# modbus_rtu_io.net
KiCad netlist of a schematic drawn in EAGLE
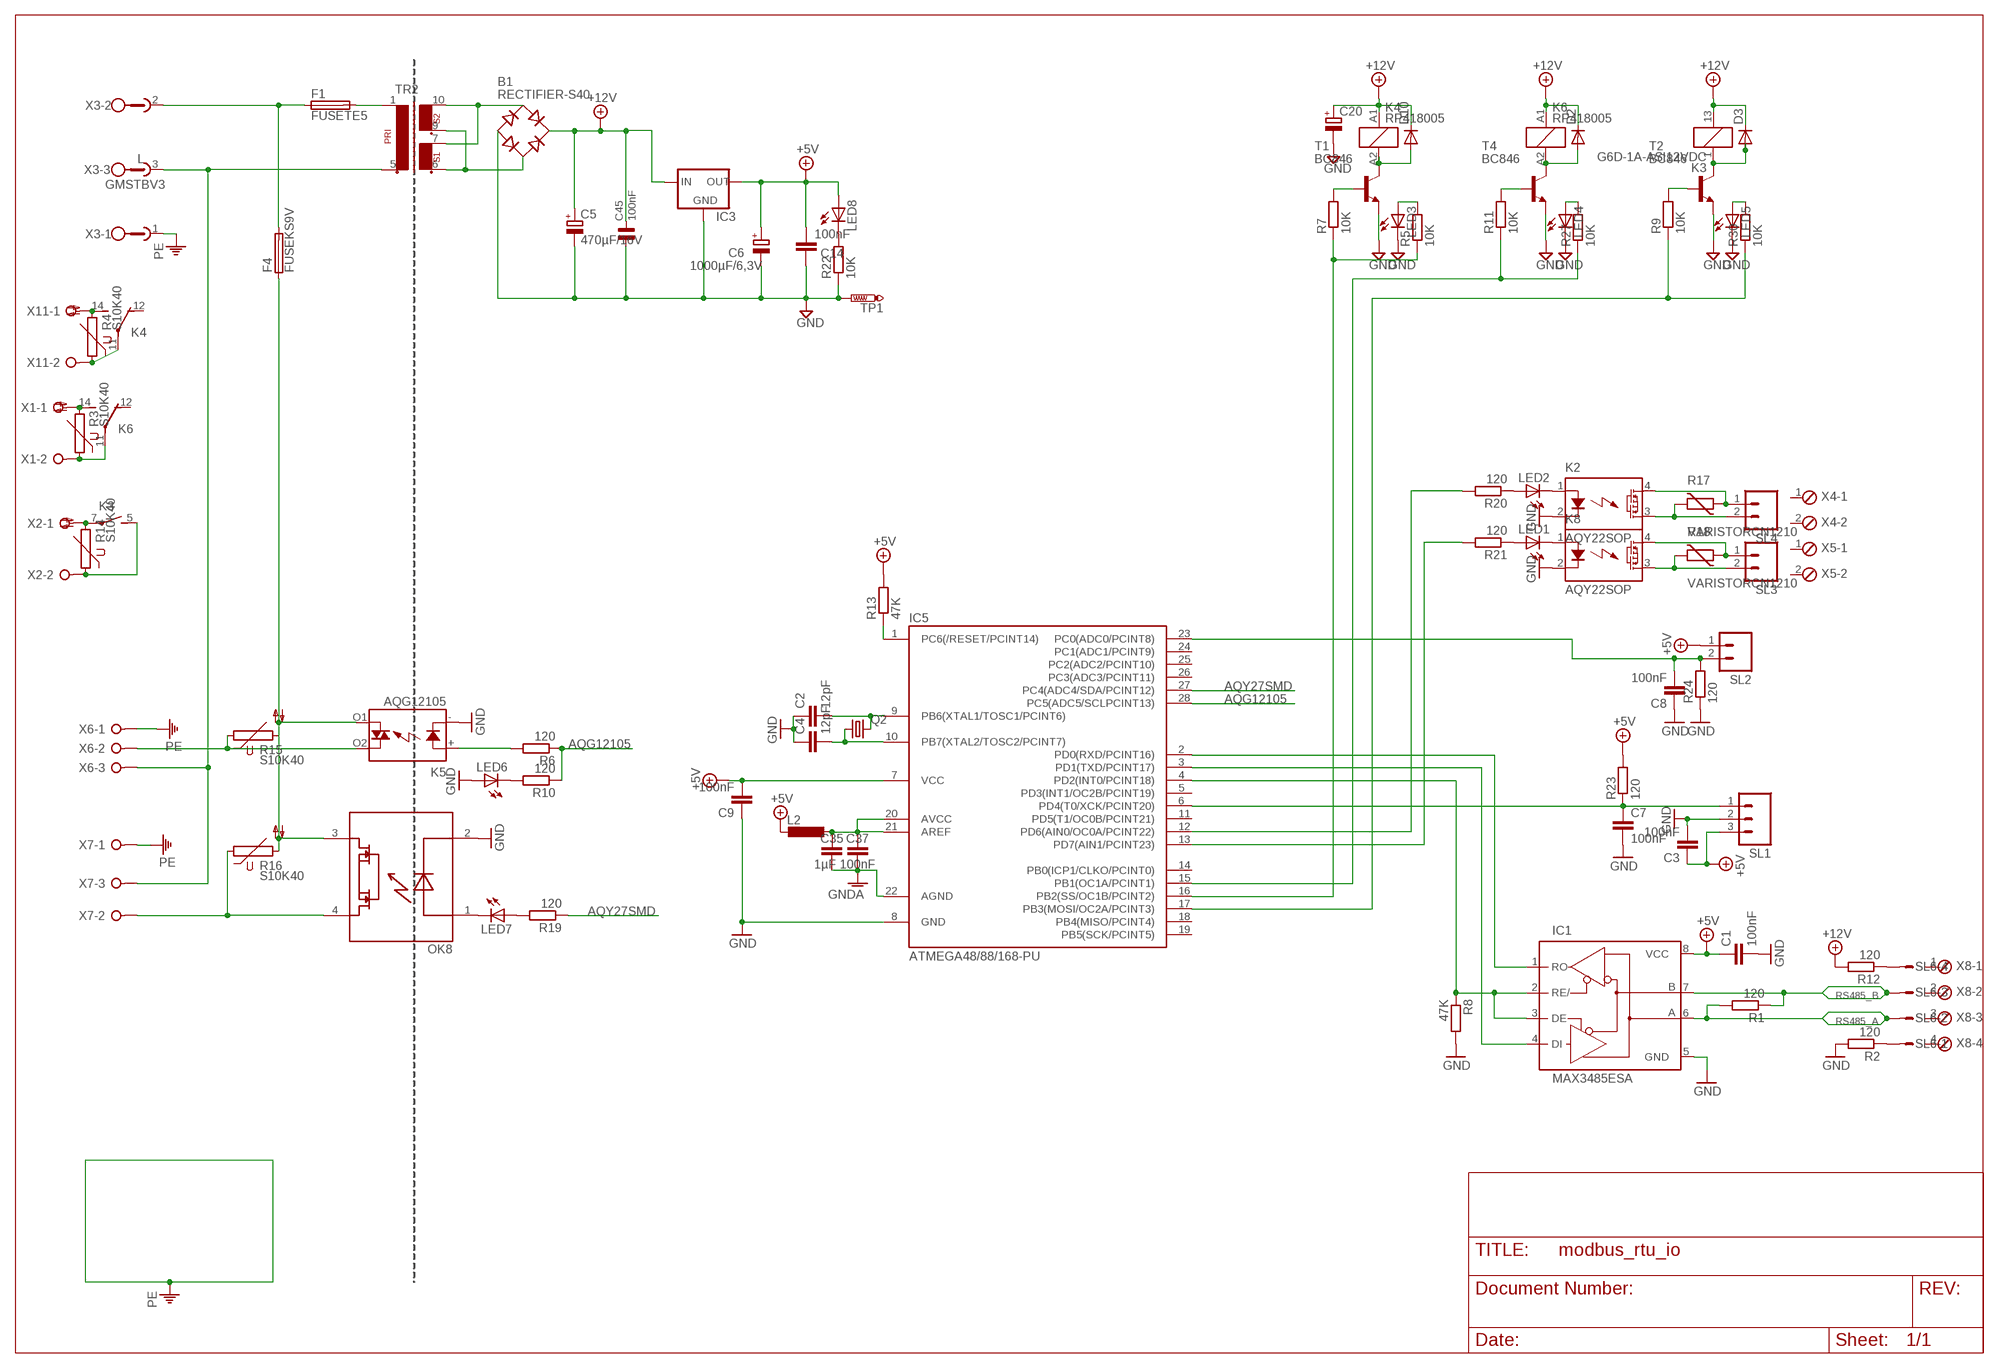
[diagram p0: schematic, sheet 1]

(export (version "E")
  (design (tool "Eeschema 10.0.6"))
  (components
    (comp (ref "B1")
      (value "RECTIFIER-S40")
      (footprint "eagle-import:TO-269AA")
      (libsource (lib "eagle-import") (part "RECTIFIER-S40"))
    )
    (comp (ref "C1")
      (value "100nF")
      (footprint "eagle-import:C0603")
      (libsource (lib "eagle-import") (part "C-EUC0603"))
    )
    (comp (ref "C2")
      (value "12pF")
      (footprint "eagle-import:C0805")
      (libsource (lib "eagle-import") (part "C-EUC0805"))
    )
    (comp (ref "C3")
      (value "100nF")
      (footprint "eagle-import:C0603")
      (libsource (lib "eagle-import") (part "C-EUC0603"))
    )
    (comp (ref "C4")
      (value "12pF")
      (footprint "eagle-import:C0805")
      (libsource (lib "eagle-import") (part "C-EUC0805"))
    )
    (comp (ref "C5")
      (value "470µF/16V")
      (footprint "eagle-import:E3,5-8")
      (libsource (lib "eagle-import") (part "CPOL-EUE3.5-8"))
    )
    (comp (ref "C6")
      (value "1000µF/6,3V")
      (footprint "eagle-import:E3,5-8")
      (libsource (lib "eagle-import") (part "CPOL-EUE3.5-8"))
    )
    (comp (ref "C7")
      (value "100nF")
      (footprint "eagle-import:C0603")
      (libsource (lib "eagle-import") (part "C-EUC0603"))
    )
    (comp (ref "C8")
      (value "100nF")
      (footprint "eagle-import:C0603")
      (libsource (lib "eagle-import") (part "C-EUC0603"))
    )
    (comp (ref "C9")
      (value "100nF")
      (footprint "eagle-import:C0603")
      (libsource (lib "eagle-import") (part "C-EUC0603"))
    )
    (comp (ref "C14")
      (value "100nF")
      (footprint "eagle-import:C1206")
      (libsource (lib "eagle-import") (part "C-EUC1206"))
    )
    (comp (ref "C20")
      (value "CPOL-EUE3.5-8")
      (footprint "eagle-import:E3,5-8")
      (libsource (lib "eagle-import") (part "CPOL-EUE3.5-8"))
    )
    (comp (ref "C35")
      (value "1µF")
      (footprint "eagle-import:C0603")
      (libsource (lib "eagle-import") (part "rcl-2_C-EUC0603"))
    )
    (comp (ref "C37")
      (value "100nF")
      (footprint "eagle-import:C0603")
      (libsource (lib "eagle-import") (part "rcl-2_C-EUC0603"))
    )
    (comp (ref "C45")
      (value "100nF")
      (footprint "eagle-import:C0805")
      (libsource (lib "eagle-import") (part "C0805"))
    )
    (comp (ref "D2")
      (value "DIODE-MINIMELF")
      (footprint "eagle-import:MINIMELF")
      (libsource (lib "eagle-import") (part "DIODE-MINIMELF"))
    )
    (comp (ref "D3")
      (value "DIODE-MINIMELF")
      (footprint "eagle-import:MINIMELF")
      (libsource (lib "eagle-import") (part "DIODE-MINIMELF"))
    )
    (comp (ref "D10")
      (value "DIODE-MINIMELF")
      (footprint "eagle-import:MINIMELF")
      (libsource (lib "eagle-import") (part "DIODE-MINIMELF"))
    )
    (comp (ref "F1")
      (value "FUSETE5")
      (footprint "eagle-import:TE5")
      (libsource (lib "eagle-import") (part "FUSETE5"))
    )
    (comp (ref "F4")
      (value "FUSEKS9V")
      (footprint "eagle-import:KS9V")
      (libsource (lib "eagle-import") (part "FUSEKS9V"))
    )
    (comp (ref "IC1")
      (value "MAX3485ESA")
      (footprint "eagle-import:SO08")
      (libsource (lib "eagle-import") (part "MAX34SA69E"))
    )
    (comp (ref "IC3")
      (value "78XXS")
      (footprint "eagle-import:78XXS")
      (libsource (lib "eagle-import") (part "78XXS"))
    )
    (comp (ref "IC5")
      (value "ATMEGA48/88/168-PU")
      (footprint "eagle-import:DIL28-3")
      (libsource (lib "eagle-import") (part "ATMEGA48/88/168-PU"))
    )
    (comp (ref "K2")
      (value "AQY22SOP")
      (footprint "eagle-import:SOP04")
      (libsource (lib "eagle-import") (part "AQYSOP22"))
    )
    (comp (ref "K3")
      (value "G6D-1A-ASI12VDC")
      (footprint "eagle-import:G6D")
      (libsource (lib "eagle-import") (part "G6D?-1A-ASI12VDC"))
    )
    (comp (ref "K4")
      (value "RP418005")
      (footprint "eagle-import:RT-C_O12A3.5")
      (libsource (lib "eagle-import") (part "RP?184005"))
    )
    (comp (ref "K5")
      (value "AQG12105")
      (footprint "eagle-import:AQG")
      (fields (field (name "MF") "AROMAT/ MATSUSHITA"))
      (libsource (lib "eagle-import") (part "AQG12105"))
    )
    (comp (ref "K6")
      (value "RP418005")
      (footprint "eagle-import:RT-C_O12A3.5")
      (libsource (lib "eagle-import") (part "RP?184005"))
    )
    (comp (ref "K8")
      (value "AQY22SOP")
      (footprint "eagle-import:SOP04")
      (libsource (lib "eagle-import") (part "AQYSOP22"))
    )
    (comp (ref "L2")
      (value "L-EUL0805")
      (footprint "eagle-import:L0805")
      (libsource (lib "eagle-import") (part "L-EUL0805"))
    )
    (comp (ref "LED1")
      (value "LED3MM")
      (footprint "eagle-import:LED3MM")
      (libsource (lib "eagle-import") (part "LED3MM"))
    )
    (comp (ref "LED2")
      (value "LED3MM")
      (footprint "eagle-import:LED3MM")
      (libsource (lib "eagle-import") (part "LED3MM"))
    )
    (comp (ref "LED3")
      (value "LED3MM")
      (footprint "eagle-import:LED3MM")
      (libsource (lib "eagle-import") (part "LED3MM"))
    )
    (comp (ref "LED4")
      (value "LED3MM")
      (footprint "eagle-import:LED3MM")
      (libsource (lib "eagle-import") (part "LED3MM"))
    )
    (comp (ref "LED5")
      (value "LED3MM")
      (footprint "eagle-import:LED3MM")
      (libsource (lib "eagle-import") (part "LED3MM"))
    )
    (comp (ref "LED6")
      (value "LED3MM")
      (footprint "eagle-import:LED3MM")
      (libsource (lib "eagle-import") (part "LED3MM"))
    )
    (comp (ref "LED7")
      (value "LED3MM")
      (footprint "eagle-import:LED3MM")
      (libsource (lib "eagle-import") (part "LED3MM"))
    )
    (comp (ref "LED8")
      (value "LED3MM")
      (footprint "eagle-import:LED3MM")
      (libsource (lib "eagle-import") (part "LED3MM"))
    )
    (comp (ref "OK8")
      (value "AQY280")
      (footprint "eagle-import:DIL4-SMD")
      (libsource (lib "eagle-import") (part "AQY280"))
    )
    (comp (ref "Q2")
      (value "CRYTALHC49S")
      (footprint "eagle-import:HC49_S")
      (libsource (lib "eagle-import") (part "CRYTALHC49S"))
    )
    (comp (ref "R1")
      (value "120")
      (footprint "eagle-import:R0603")
      (libsource (lib "eagle-import") (part "R-EU_R0603"))
    )
    (comp (ref "R2")
      (value "120")
      (footprint "eagle-import:R0603")
      (libsource (lib "eagle-import") (part "R-EU_R0603"))
    )
    (comp (ref "R3")
      (value "S10K40")
      (footprint "eagle-import:S10K40")
      (libsource (lib "eagle-import") (part "S10K40"))
    )
    (comp (ref "R4")
      (value "S10K40")
      (footprint "eagle-import:S10K40")
      (libsource (lib "eagle-import") (part "S10K40"))
    )
    (comp (ref "R5")
      (value "10K")
      (footprint "eagle-import:R0603")
      (libsource (lib "eagle-import") (part "R-EU_R0603"))
    )
    (comp (ref "R6")
      (value "120")
      (footprint "eagle-import:R0603")
      (libsource (lib "eagle-import") (part "R-EU_R0603"))
    )
    (comp (ref "R7")
      (value "10K")
      (footprint "eagle-import:R0603")
      (libsource (lib "eagle-import") (part "R-EU_R0603"))
    )
    (comp (ref "R8")
      (value "47K")
      (footprint "eagle-import:R0603")
      (libsource (lib "eagle-import") (part "R-EU_R0603"))
    )
    (comp (ref "R9")
      (value "10K")
      (footprint "eagle-import:R0603")
      (libsource (lib "eagle-import") (part "R-EU_R0603"))
    )
    (comp (ref "R10")
      (value "120")
      (footprint "eagle-import:R0603")
      (libsource (lib "eagle-import") (part "R-EU_R0603"))
    )
    (comp (ref "R11")
      (value "10K")
      (footprint "eagle-import:R0603")
      (libsource (lib "eagle-import") (part "R-EU_R0603"))
    )
    (comp (ref "R12")
      (value "120")
      (footprint "eagle-import:R0603")
      (libsource (lib "eagle-import") (part "R-EU_R0603"))
    )
    (comp (ref "R13")
      (value "47K")
      (footprint "eagle-import:R0603")
      (libsource (lib "eagle-import") (part "R-EU_R0603"))
    )
    (comp (ref "R14")
      (value "S10K40")
      (footprint "eagle-import:S10K40")
      (libsource (lib "eagle-import") (part "S10K40"))
    )
    (comp (ref "R15")
      (value "S10K40")
      (footprint "eagle-import:S10K40")
      (libsource (lib "eagle-import") (part "S10K40"))
    )
    (comp (ref "R16")
      (value "S10K40")
      (footprint "eagle-import:S10K40")
      (libsource (lib "eagle-import") (part "S10K40"))
    )
    (comp (ref "R17")
      (value "VARISTORCN1210")
      (footprint "eagle-import:CT_CN1210")
      (libsource (lib "eagle-import") (part "VARISTORCN1210"))
    )
    (comp (ref "R18")
      (value "VARISTORCN1210")
      (footprint "eagle-import:CT_CN1210")
      (libsource (lib "eagle-import") (part "VARISTORCN1210"))
    )
    (comp (ref "R19")
      (value "120")
      (footprint "eagle-import:R0603")
      (libsource (lib "eagle-import") (part "R-EU_R0603"))
    )
    (comp (ref "R20")
      (value "120")
      (footprint "eagle-import:R0603")
      (libsource (lib "eagle-import") (part "R-EU_R0603"))
    )
    (comp (ref "R21")
      (value "120")
      (footprint "eagle-import:R0603")
      (libsource (lib "eagle-import") (part "R-EU_R0603"))
    )
    (comp (ref "R22")
      (value "10K")
      (footprint "eagle-import:R0603")
      (libsource (lib "eagle-import") (part "R-EU_R0603"))
    )
    (comp (ref "R23")
      (value "120")
      (footprint "eagle-import:R0603")
      (libsource (lib "eagle-import") (part "R-EU_R0603"))
    )
    (comp (ref "R24")
      (value "120")
      (footprint "eagle-import:R0603")
      (libsource (lib "eagle-import") (part "R-EU_R0603"))
    )
    (comp (ref "R27")
      (value "10K")
      (footprint "eagle-import:R0603")
      (libsource (lib "eagle-import") (part "R-EU_R0603"))
    )
    (comp (ref "R30")
      (value "10K")
      (footprint "eagle-import:R0603")
      (libsource (lib "eagle-import") (part "R-EU_R0603"))
    )
    (comp (ref "SL1")
      (value "M03")
      (footprint "eagle-import:03P")
      (libsource (lib "eagle-import") (part "M03"))
    )
    (comp (ref "SL2")
      (value "M02")
      (footprint "eagle-import:02P")
      (libsource (lib "eagle-import") (part "M02"))
    )
    (comp (ref "SL3")
      (value "M02")
      (footprint "eagle-import:02P")
      (libsource (lib "eagle-import") (part "M02"))
    )
    (comp (ref "SL4")
      (value "M02")
      (footprint "eagle-import:02P")
      (libsource (lib "eagle-import") (part "M02"))
    )
    (comp (ref "SL6")
      (value "M04S")
      (footprint "eagle-import:04P")
      (libsource (lib "eagle-import") (part "M04S"))
    )
    (comp (ref "T1")
      (value "BC846")
      (footprint "eagle-import:SOT23")
      (libsource (lib "eagle-import") (part "BC846"))
    )
    (comp (ref "T2")
      (value "BC846")
      (footprint "eagle-import:SOT23")
      (libsource (lib "eagle-import") (part "BC846"))
    )
    (comp (ref "T4")
      (value "BC846")
      (footprint "eagle-import:SOT23")
      (libsource (lib "eagle-import") (part "BC846"))
    )
    (comp (ref "TP1")
      (value "PTR1PAD1-13")
      (footprint "eagle-import:P1-13")
      (libsource (lib "eagle-import") (part "PTR1PAD1-13"))
    )
    (comp (ref "TR2")
      (value "EI30-2")
      (footprint "eagle-import:EI30-2")
      (libsource (lib "eagle-import") (part "EI30-2"))
    )
    (comp (ref "X1")
      (value "W237-02P")
      (footprint "eagle-import:W237-132")
      (libsource (lib "eagle-import") (part "W237-02P"))
    )
    (comp (ref "X2")
      (value "W237-02P")
      (footprint "eagle-import:W237-132")
      (libsource (lib "eagle-import") (part "W237-02P"))
    )
    (comp (ref "X3")
      (value "GMSTBV3")
      (footprint "eagle-import:GMSTBV3")
      (fields (field (name "MPN") "GMSTBVA2,5/3-G-7,62"))
      (libsource (lib "eagle-import") (part "GMSTBV3"))
    )
    (comp (ref "X4")
      (value "MPT2")
      (footprint "eagle-import:2POL254")
      (libsource (lib "eagle-import") (part "MPT2"))
    )
    (comp (ref "X5")
      (value "MPT2")
      (footprint "eagle-import:2POL254")
      (libsource (lib "eagle-import") (part "MPT2"))
    )
    (comp (ref "X6")
      (value "W237-03P")
      (footprint "eagle-import:W237-133")
      (libsource (lib "eagle-import") (part "W237-03P"))
    )
    (comp (ref "X7")
      (value "W237-03P")
      (footprint "eagle-import:W237-133")
      (libsource (lib "eagle-import") (part "W237-03P"))
    )
    (comp (ref "X8")
      (value "MPT4")
      (footprint "eagle-import:4POL254")
      (libsource (lib "eagle-import") (part "MPT4"))
    )
    (comp (ref "X11")
      (value "W237-02P")
      (footprint "eagle-import:W237-132")
      (libsource (lib "eagle-import") (part "W237-02P"))
    )
  )
  (nets
    (net (code "1") (name "+5V") (class "Default")
      (node (ref "C1") (pin "1") (pinfunction "1_1") (pintype "passive"))
      (node (ref "C14") (pin "2") (pinfunction "2_2") (pintype "passive"))
      (node (ref "C3") (pin "1") (pinfunction "1_1") (pintype "passive"))
      (node (ref "C6") (pin "+") (pinfunction "+_+") (pintype "passive"))
      (node (ref "C9") (pin "2") (pinfunction "2_2") (pintype "passive"))
      (node (ref "IC1") (pin "8") (pinfunction "VCC_8") (pintype "power_in"))
      (node (ref "IC3") (pin "OUT") (pinfunction "OUT_OUT") (pintype "passive"))
      (node (ref "IC5") (pin "7") (pinfunction "VCC_7") (pintype "power_in"))
      (node (ref "L2") (pin "2") (pinfunction "2_2") (pintype "passive"))
      (node (ref "LED8") (pin "A") (pinfunction "A_A") (pintype "passive"))
      (node (ref "R13") (pin "2") (pinfunction "2_2") (pintype "passive"))
      (node (ref "R23") (pin "2") (pinfunction "2_2") (pintype "passive"))
      (node (ref "SL1") (pin "3") (pinfunction "3_3") (pintype "passive"))
      (node (ref "SL2") (pin "1") (pinfunction "1_1") (pintype "passive"))
    )
    (net (code "2") (name "+12V") (class "Default")
      (node (ref "B1") (pin "+") (pinfunction "+_+") (pintype "passive"))
      (node (ref "C20") (pin "+") (pinfunction "+_+") (pintype "passive"))
      (node (ref "C45") (pin "2") (pinfunction "2_2") (pintype "passive"))
      (node (ref "C5") (pin "+") (pinfunction "+_+") (pintype "passive"))
      (node (ref "D10") (pin "C") (pinfunction "C_C") (pintype "passive"))
      (node (ref "D2") (pin "C") (pinfunction "C_C") (pintype "passive"))
      (node (ref "D3") (pin "C") (pinfunction "C_C") (pintype "passive"))
      (node (ref "IC3") (pin "IN") (pinfunction "IN_IN") (pintype "input"))
      (node (ref "K3") (pin "13") (pinfunction "2_13") (pintype "passive"))
      (node (ref "K4") (pin "A1") (pinfunction "1_A1") (pintype "passive"))
      (node (ref "K6") (pin "A1") (pinfunction "1_A1") (pintype "passive"))
      (node (ref "R12") (pin "2") (pinfunction "2_2") (pintype "passive"))
    )
    (net (code "3") (name "/AQG12105") (class "Default")
      (node (ref "IC5") (pin "28") (pinfunction "PC5(ADC5/SCLPCINT13)_28") (pintype "bidirectional"))
      (node (ref "R10") (pin "1") (pinfunction "1_1") (pintype "passive"))
      (node (ref "R6") (pin "1") (pinfunction "1_1") (pintype "passive"))
    )
    (net (code "4") (name "/AQY27SMD") (class "Default")
      (node (ref "IC5") (pin "27") (pinfunction "PC4(ADC4/SDA/PCINT12)_27") (pintype "bidirectional"))
      (node (ref "R19") (pin "1") (pinfunction "1_1") (pintype "passive"))
    )
    (net (code "5") (name "/L") (class "Default")
      (node (ref "F1") (pin "1") (pinfunction "1_1") (pintype "passive"))
      (node (ref "F4") (pin "2") (pinfunction "2_2") (pintype "passive"))
      (node (ref "X3") (pin "2") (pinfunction "1_2") (pintype "passive"))
    )
    (net (code "6") (name "/RS485_A") (class "Default")
      (node (ref "IC1") (pin "6") (pinfunction "A_6") (pintype "passive"))
      (node (ref "R1") (pin "2") (pinfunction "2_2") (pintype "passive"))
      (node (ref "SL6") (pin "2") (pinfunction "S_2") (pintype "passive"))
    )
    (net (code "7") (name "/RS485_B") (class "Default")
      (node (ref "IC1") (pin "7") (pinfunction "B_7") (pintype "passive"))
      (node (ref "R1") (pin "1") (pinfunction "1_1") (pintype "passive"))
      (node (ref "SL6") (pin "3") (pinfunction "S_3") (pintype "passive"))
    )
    (net (code "8") (name "GND") (class "Default")
      (node (ref "B1") (pin "-") (pinfunction "-_-") (pintype "passive"))
      (node (ref "C1") (pin "2") (pinfunction "2_2") (pintype "passive"))
      (node (ref "C14") (pin "1") (pinfunction "1_1") (pintype "passive"))
      (node (ref "C2") (pin "1") (pinfunction "1_1") (pintype "passive"))
      (node (ref "C20") (pin "-") (pinfunction "-_-") (pintype "passive"))
      (node (ref "C3") (pin "2") (pinfunction "2_2") (pintype "passive"))
      (node (ref "C4") (pin "1") (pinfunction "1_1") (pintype "passive"))
      (node (ref "C45") (pin "1") (pinfunction "1_1") (pintype "passive"))
      (node (ref "C5") (pin "-") (pinfunction "-_-") (pintype "passive"))
      (node (ref "C6") (pin "-") (pinfunction "-_-") (pintype "passive"))
      (node (ref "C7") (pin "2") (pinfunction "2_2") (pintype "passive"))
      (node (ref "C8") (pin "1") (pinfunction "1_1") (pintype "passive"))
      (node (ref "C9") (pin "1") (pinfunction "1_1") (pintype "passive"))
      (node (ref "IC1") (pin "5") (pinfunction "GND_5") (pintype "power_in"))
      (node (ref "IC3") (pin "GND") (pinfunction "GND_GND") (pintype "input"))
      (node (ref "IC5") (pin "8") (pinfunction "GND_8") (pintype "power_in"))
      (node (ref "K2") (pin "2") (pinfunction "K_2") (pintype "passive"))
      (node (ref "K5") (pin "-") (pinfunction "K_-") (pintype "passive"))
      (node (ref "K8") (pin "2") (pinfunction "K_2") (pintype "passive"))
      (node (ref "LED3") (pin "K") (pinfunction "C_K") (pintype "passive"))
      (node (ref "LED4") (pin "K") (pinfunction "C_K") (pintype "passive"))
      (node (ref "LED5") (pin "K") (pinfunction "C_K") (pintype "passive"))
      (node (ref "LED6") (pin "A") (pinfunction "A_A") (pintype "passive"))
      (node (ref "OK8") (pin "2") (pinfunction "2_2") (pintype "passive"))
      (node (ref "R2") (pin "2") (pinfunction "2_2") (pintype "passive"))
      (node (ref "R22") (pin "1") (pinfunction "1_1") (pintype "passive"))
      (node (ref "R24") (pin "1") (pinfunction "1_1") (pintype "passive"))
      (node (ref "R8") (pin "2") (pinfunction "2_2") (pintype "passive"))
      (node (ref "SL1") (pin "2") (pinfunction "2_2") (pintype "passive"))
      (node (ref "T1") (pin "2") (pinfunction "E_2") (pintype "passive"))
      (node (ref "T2") (pin "2") (pinfunction "E_2") (pintype "passive"))
      (node (ref "T4") (pin "2") (pinfunction "E_2") (pintype "passive"))
      (node (ref "TP1") (pin "TP") (pinfunction "TP_TP") (pintype "input"))
    )
    (net (code "9") (name "GNDA") (class "Default")
      (node (ref "C35") (pin "2") (pinfunction "2_2") (pintype "passive"))
      (node (ref "C37") (pin "2") (pinfunction "2_2") (pintype "passive"))
      (node (ref "IC5") (pin "22") (pinfunction "AGND_22") (pintype "power_in"))
    )
    (net (code "10") (name "Net-(F1-Pad2)") (class "Default")
      (node (ref "F1") (pin "2") (pinfunction "2_2") (pintype "passive"))
      (node (ref "TR2") (pin "1") (pinfunction "1_1") (pintype "passive"))
    )
    (net (code "11") (name "Net-(IC1-DE)") (class "Default")
      (node (ref "IC1") (pin "2") (pinfunction "RE/_2") (pintype "input"))
      (node (ref "IC1") (pin "3") (pinfunction "DE_3") (pintype "input"))
      (node (ref "IC5") (pin "4") (pinfunction "PD2(INT0/PCINT18)_4") (pintype "bidirectional"))
      (node (ref "R8") (pin "1") (pinfunction "1_1") (pintype "passive"))
    )
    (net (code "12") (name "Net-(IC1-DI)") (class "Default")
      (node (ref "IC1") (pin "4") (pinfunction "DI_4") (pintype "input"))
      (node (ref "IC5") (pin "3") (pinfunction "PD1(TXD/PCINT17)_3") (pintype "bidirectional"))
    )
    (net (code "13") (name "Net-(IC1-RO)") (class "Default")
      (node (ref "IC1") (pin "1") (pinfunction "RO_1") (pintype "output"))
      (node (ref "IC5") (pin "2") (pinfunction "PD0(RXD/PCINT16)_2") (pintype "bidirectional"))
    )
    (net (code "14") (name "Net-(IC5-AREF)") (class "Default")
      (node (ref "C35") (pin "1") (pinfunction "1_1") (pintype "passive"))
      (node (ref "C37") (pin "1") (pinfunction "1_1") (pintype "passive"))
      (node (ref "IC5") (pin "20") (pinfunction "AVCC_20") (pintype "passive"))
      (node (ref "IC5") (pin "21") (pinfunction "AREF_21") (pintype "passive"))
      (node (ref "L2") (pin "1") (pinfunction "1_1") (pintype "passive"))
    )
    (net (code "15") (name "Net-(IC5-PB1(OC1A{slash}PCINT1))") (class "Default")
      (node (ref "IC5") (pin "15") (pinfunction "PB1(OC1A/PCINT1)_15") (pintype "bidirectional"))
      (node (ref "R11") (pin "1") (pinfunction "1_1") (pintype "passive"))
      (node (ref "R27") (pin "1") (pinfunction "1_1") (pintype "passive"))
    )
    (net (code "16") (name "Net-(IC5-PB2(SS{slash}OC1B{slash}PCINT2))") (class "Default")
      (node (ref "IC5") (pin "16") (pinfunction "PB2(SS/OC1B/PCINT2)_16") (pintype "bidirectional"))
      (node (ref "R5") (pin "1") (pinfunction "1_1") (pintype "passive"))
      (node (ref "R7") (pin "1") (pinfunction "1_1") (pintype "passive"))
    )
    (net (code "17") (name "Net-(IC5-PB3(MOSI{slash}OC2A{slash}PCINT3))") (class "Default")
      (node (ref "IC5") (pin "17") (pinfunction "PB3(MOSI/OC2A/PCINT3)_17") (pintype "bidirectional"))
      (node (ref "R30") (pin "1") (pinfunction "1_1") (pintype "passive"))
      (node (ref "R9") (pin "1") (pinfunction "1_1") (pintype "passive"))
    )
    (net (code "18") (name "Net-(IC5-PB6(XTAL1{slash}TOSC1{slash}PCINT6))") (class "Default")
      (node (ref "C2") (pin "2") (pinfunction "2_2") (pintype "passive"))
      (node (ref "IC5") (pin "9") (pinfunction "PB6(XTAL1/TOSC1/PCINT6)_9") (pintype "bidirectional"))
      (node (ref "Q2") (pin "2") (pinfunction "2_2") (pintype "passive"))
    )
    (net (code "19") (name "Net-(IC5-PB7(XTAL2{slash}TOSC2{slash}PCINT7))") (class "Default")
      (node (ref "C4") (pin "2") (pinfunction "2_2") (pintype "passive"))
      (node (ref "IC5") (pin "10") (pinfunction "PB7(XTAL2/TOSC2/PCINT7)_10") (pintype "bidirectional"))
      (node (ref "Q2") (pin "1") (pinfunction "1_1") (pintype "passive"))
    )
    (net (code "20") (name "Net-(IC5-PC0(ADC0{slash}PCINT8))") (class "Default")
      (node (ref "C8") (pin "2") (pinfunction "2_2") (pintype "passive"))
      (node (ref "IC5") (pin "23") (pinfunction "PC0(ADC0/PCINT8)_23") (pintype "bidirectional"))
      (node (ref "R24") (pin "2") (pinfunction "2_2") (pintype "passive"))
      (node (ref "SL2") (pin "2") (pinfunction "2_2") (pintype "passive"))
    )
    (net (code "21") (name "Net-(IC5-PC6({slash}RESET{slash}PCINT14))") (class "Default")
      (node (ref "IC5") (pin "1") (pinfunction "PC6(/RESET/PCINT14)_1") (pintype "bidirectional"))
      (node (ref "R13") (pin "1") (pinfunction "1_1") (pintype "passive"))
    )
    (net (code "22") (name "Net-(IC5-PD4(T0{slash}XCK{slash}PCINT20))") (class "Default")
      (node (ref "C7") (pin "1") (pinfunction "1_1") (pintype "passive"))
      (node (ref "IC5") (pin "6") (pinfunction "PD4(T0/XCK/PCINT20)_6") (pintype "bidirectional"))
      (node (ref "R23") (pin "1") (pinfunction "1_1") (pintype "passive"))
      (node (ref "SL1") (pin "1") (pinfunction "1_1") (pintype "passive"))
    )
    (net (code "23") (name "Net-(IC5-PD6(AIN0{slash}OC0A{slash}PCINT22))") (class "Default")
      (node (ref "IC5") (pin "12") (pinfunction "PD6(AIN0/OC0A/PCINT22)_12") (pintype "bidirectional"))
      (node (ref "R20") (pin "2") (pinfunction "2_2") (pintype "passive"))
    )
    (net (code "24") (name "Net-(IC5-PD7(AIN1{slash}PCINT23))") (class "Default")
      (node (ref "IC5") (pin "13") (pinfunction "PD7(AIN1/PCINT23)_13") (pintype "bidirectional"))
      (node (ref "R21") (pin "2") (pinfunction "2_2") (pintype "passive"))
    )
    (net (code "25") (name "Net-(K2-A)") (class "Default")
      (node (ref "K2") (pin "1") (pinfunction "A_1") (pintype "passive"))
      (node (ref "LED2") (pin "K") (pinfunction "C_K") (pintype "passive"))
    )
    (net (code "26") (name "Net-(K2-DS1)") (class "Default")
      (node (ref "K2") (pin "4") (pinfunction "DS1_4") (pintype "passive"))
      (node (ref "R17") (pin "1") (pinfunction "1_1") (pintype "passive"))
      (node (ref "SL4") (pin "1") (pinfunction "1_1") (pintype "passive"))
    )
    (net (code "27") (name "Net-(K2-DS2)") (class "Default")
      (node (ref "K2") (pin "3") (pinfunction "DS2_3") (pintype "passive"))
      (node (ref "R17") (pin "2") (pinfunction "2_2") (pintype "passive"))
      (node (ref "SL4") (pin "2") (pinfunction "2_2") (pintype "passive"))
    )
    (net (code "28") (name "Net-(K3B-P)") (class "Default")
      (node (ref "K3") (pin "7") (pinfunction "P_7") (pintype "passive"))
      (node (ref "R14") (pin "2") (pinfunction "2_2") (pintype "passive"))
      (node (ref "X2") (pin "1") (pinfunction "KL_1") (pintype "passive"))
    )
    (net (code "29") (name "Net-(K3B-S)") (class "Default")
      (node (ref "K3") (pin "5") (pinfunction "S_5") (pintype "passive"))
      (node (ref "R14") (pin "1") (pinfunction "1_1") (pintype "passive"))
      (node (ref "X2") (pin "2") (pinfunction "KL_2") (pintype "passive"))
    )
    (net (code "30") (name "Net-(K4A-2)") (class "Default")
      (node (ref "D10") (pin "A") (pinfunction "A_A") (pintype "passive"))
      (node (ref "K4") (pin "A2") (pinfunction "2_A2") (pintype "passive"))
      (node (ref "T1") (pin "3") (pinfunction "C_3") (pintype "passive"))
    )
    (net (code "31") (name "Net-(K4B-P)") (class "Default")
      (node (ref "K4") (pin "11") (pinfunction "P_11") (pintype "passive"))
      (node (ref "R4") (pin "1") (pinfunction "1_1") (pintype "passive"))
      (node (ref "X11") (pin "2") (pinfunction "KL_2") (pintype "passive"))
    )
    (net (code "32") (name "Net-(K4B-S)") (class "Default")
      (node (ref "K4") (pin "14") (pinfunction "S_14") (pintype "passive"))
      (node (ref "R4") (pin "2") (pinfunction "2_2") (pintype "passive"))
      (node (ref "X11") (pin "1") (pinfunction "KL_1") (pintype "passive"))
    )
    (net (code "33") (name "Net-(K5-A)") (class "Default")
      (node (ref "K5") (pin "+") (pinfunction "A_+") (pintype "passive"))
      (node (ref "R6") (pin "2") (pinfunction "2_2") (pintype "passive"))
    )
    (net (code "34") (name "Net-(K5-DS1)") (class "Default")
      (node (ref "K5") (pin "O2") (pinfunction "DS1_O2") (pintype "passive"))
      (node (ref "R15") (pin "1") (pinfunction "1_1") (pintype "passive"))
      (node (ref "X6") (pin "2") (pinfunction "KL_2") (pintype "passive"))
    )
    (net (code "35") (name "Net-(K5-DS2)") (class "Default")
      (node (ref "F4") (pin "1") (pinfunction "1_1") (pintype "passive"))
      (node (ref "K5") (pin "O1") (pinfunction "DS2_O1") (pintype "passive"))
      (node (ref "OK8") (pin "3") (pinfunction "3_3") (pintype "passive"))
      (node (ref "R15") (pin "2") (pinfunction "2_2") (pintype "passive"))
      (node (ref "R16") (pin "2") (pinfunction "2_2") (pintype "passive"))
    )
    (net (code "36") (name "Net-(K6A-2)") (class "Default")
      (node (ref "D2") (pin "A") (pinfunction "A_A") (pintype "passive"))
      (node (ref "K6") (pin "A2") (pinfunction "2_A2") (pintype "passive"))
      (node (ref "T4") (pin "3") (pinfunction "C_3") (pintype "passive"))
    )
    (net (code "37") (name "Net-(K6B-P)") (class "Default")
      (node (ref "K6") (pin "11") (pinfunction "P_11") (pintype "passive"))
      (node (ref "R3") (pin "1") (pinfunction "1_1") (pintype "passive"))
      (node (ref "X1") (pin "2") (pinfunction "KL_2") (pintype "passive"))
    )
    (net (code "38") (name "Net-(K6B-S)") (class "Default")
      (node (ref "K6") (pin "14") (pinfunction "S_14") (pintype "passive"))
      (node (ref "R3") (pin "2") (pinfunction "2_2") (pintype "passive"))
      (node (ref "X1") (pin "1") (pinfunction "KL_1") (pintype "passive"))
    )
    (net (code "39") (name "Net-(K8-A)") (class "Default")
      (node (ref "K8") (pin "1") (pinfunction "A_1") (pintype "passive"))
      (node (ref "LED1") (pin "K") (pinfunction "C_K") (pintype "passive"))
    )
    (net (code "40") (name "Net-(K8-DS1)") (class "Default")
      (node (ref "K8") (pin "4") (pinfunction "DS1_4") (pintype "passive"))
      (node (ref "R18") (pin "1") (pinfunction "1_1") (pintype "passive"))
      (node (ref "SL3") (pin "1") (pinfunction "1_1") (pintype "passive"))
    )
    (net (code "41") (name "Net-(K8-DS2)") (class "Default")
      (node (ref "K8") (pin "3") (pinfunction "DS2_3") (pintype "passive"))
      (node (ref "R18") (pin "2") (pinfunction "2_2") (pintype "passive"))
      (node (ref "SL3") (pin "2") (pinfunction "2_2") (pintype "passive"))
    )
    (net (code "42") (name "Net-(LED1-PadA)") (class "Default")
      (node (ref "LED1") (pin "A") (pinfunction "A_A") (pintype "passive"))
      (node (ref "R21") (pin "1") (pinfunction "1_1") (pintype "passive"))
    )
    (net (code "43") (name "Net-(LED2-PadA)") (class "Default")
      (node (ref "LED2") (pin "A") (pinfunction "A_A") (pintype "passive"))
      (node (ref "R20") (pin "1") (pinfunction "1_1") (pintype "passive"))
    )
    (net (code "44") (name "Net-(LED3-PadA)") (class "Default")
      (node (ref "LED3") (pin "A") (pinfunction "A_A") (pintype "passive"))
      (node (ref "R5") (pin "2") (pinfunction "2_2") (pintype "passive"))
    )
    (net (code "45") (name "Net-(LED4-PadA)") (class "Default")
      (node (ref "LED4") (pin "A") (pinfunction "A_A") (pintype "passive"))
      (node (ref "R27") (pin "2") (pinfunction "2_2") (pintype "passive"))
    )
    (net (code "46") (name "Net-(LED5-PadA)") (class "Default")
      (node (ref "LED5") (pin "A") (pinfunction "A_A") (pintype "passive"))
      (node (ref "R30") (pin "2") (pinfunction "2_2") (pintype "passive"))
    )
    (net (code "47") (name "Net-(LED6-C)") (class "Default")
      (node (ref "LED6") (pin "K") (pinfunction "C_K") (pintype "passive"))
      (node (ref "R10") (pin "2") (pinfunction "2_2") (pintype "passive"))
    )
    (net (code "48") (name "Net-(LED7-C)") (class "Default")
      (node (ref "LED7") (pin "K") (pinfunction "C_K") (pintype "passive"))
      (node (ref "OK8") (pin "1") (pinfunction "1_1") (pintype "passive"))
    )
    (net (code "49") (name "Net-(LED7-PadA)") (class "Default")
      (node (ref "LED7") (pin "A") (pinfunction "A_A") (pintype "passive"))
      (node (ref "R19") (pin "2") (pinfunction "2_2") (pintype "passive"))
    )
    (net (code "50") (name "Net-(LED8-C)") (class "Default")
      (node (ref "LED8") (pin "K") (pinfunction "C_K") (pintype "passive"))
      (node (ref "R22") (pin "2") (pinfunction "2_2") (pintype "passive"))
    )
    (net (code "51") (name "Net-(SL6A-S)") (class "Default")
      (node (ref "R2") (pin "1") (pinfunction "1_1") (pintype "passive"))
      (node (ref "SL6") (pin "1") (pinfunction "S_1") (pintype "passive"))
    )
    (net (code "52") (name "Net-(SL6D-S)") (class "Default")
      (node (ref "R12") (pin "1") (pinfunction "1_1") (pintype "passive"))
      (node (ref "SL6") (pin "4") (pinfunction "S_4") (pintype "passive"))
    )
    (net (code "53") (name "Net-(T1-B)") (class "Default")
      (node (ref "R7") (pin "2") (pinfunction "2_2") (pintype "passive"))
      (node (ref "T1") (pin "1") (pinfunction "B_1") (pintype "passive"))
    )
    (net (code "54") (name "Net-(T2-B)") (class "Default")
      (node (ref "R9") (pin "2") (pinfunction "2_2") (pintype "passive"))
      (node (ref "T2") (pin "1") (pinfunction "B_1") (pintype "passive"))
    )
    (net (code "55") (name "Net-(T2-C)") (class "Default")
      (node (ref "D3") (pin "A") (pinfunction "A_A") (pintype "passive"))
      (node (ref "K3") (pin "1") (pinfunction "1_1") (pintype "passive"))
      (node (ref "T2") (pin "3") (pinfunction "C_3") (pintype "passive"))
    )
    (net (code "56") (name "Net-(T4-B)") (class "Default")
      (node (ref "R11") (pin "2") (pinfunction "2_2") (pintype "passive"))
      (node (ref "T4") (pin "1") (pinfunction "B_1") (pintype "passive"))
    )
    (net (code "57") (name "Net-(TR2-2)") (class "Default")
      (node (ref "TR2") (pin "5") (pinfunction "2_5") (pintype "passive"))
      (node (ref "X3") (pin "3") (pinfunction "1_3") (pintype "passive"))
      (node (ref "X6") (pin "3") (pinfunction "KL_3") (pintype "passive"))
      (node (ref "X7") (pin "3") (pinfunction "KL_3") (pintype "passive"))
    )
    (net (code "58") (name "Net-(TR2-3)") (class "Default")
      (node (ref "B1") (pin "AC2") (pinfunction "AC2_AC2") (pintype "passive"))
      (node (ref "TR2") (pin "6") (pinfunction "3_6") (pintype "passive"))
      (node (ref "TR2") (pin "9") (pinfunction "5_9") (pintype "passive"))
    )
    (net (code "59") (name "Net-(TR2-4)") (class "Default")
      (node (ref "B1") (pin "AC1") (pinfunction "AC1_AC1") (pintype "passive"))
      (node (ref "TR2") (pin "10") (pinfunction "6_10") (pintype "passive"))
      (node (ref "TR2") (pin "7") (pinfunction "4_7") (pintype "passive"))
    )
    (net (code "60") (name "Net-(X7B-KL)") (class "Default")
      (node (ref "OK8") (pin "4") (pinfunction "4_4") (pintype "passive"))
      (node (ref "R16") (pin "1") (pinfunction "1_1") (pintype "passive"))
      (node (ref "X7") (pin "2") (pinfunction "KL_2") (pintype "passive"))
    )
    (net (code "61") (name "PE") (class "Default")
      (node (ref "X3") (pin "1") (pinfunction "1_1") (pintype "passive"))
      (node (ref "X6") (pin "1") (pinfunction "KL_1") (pintype "passive"))
      (node (ref "X7") (pin "1") (pinfunction "KL_1") (pintype "passive"))
    )
    (net (code "62") (name "unconnected-(IC5-PB0(ICP1{slash}CLKO{slash}PCINT0)-Pad14)") (class "Default")
      (node (ref "IC5") (pin "14") (pinfunction "PB0(ICP1/CLKO/PCINT0)_14") (pintype "bidirectional"))
    )
    (net (code "63") (name "unconnected-(IC5-PB4(MISO{slash}PCINT4)-Pad18)") (class "Default")
      (node (ref "IC5") (pin "18") (pinfunction "PB4(MISO/PCINT4)_18") (pintype "bidirectional"))
    )
    (net (code "64") (name "unconnected-(IC5-PB5(SCK{slash}PCINT5)-Pad19)") (class "Default")
      (node (ref "IC5") (pin "19") (pinfunction "PB5(SCK/PCINT5)_19") (pintype "bidirectional"))
    )
    (net (code "65") (name "unconnected-(IC5-PC1(ADC1{slash}PCINT9)-Pad24)") (class "Default")
      (node (ref "IC5") (pin "24") (pinfunction "PC1(ADC1/PCINT9)_24") (pintype "bidirectional"))
    )
    (net (code "66") (name "unconnected-(IC5-PC2(ADC2{slash}PCINT10)-Pad25)") (class "Default")
      (node (ref "IC5") (pin "25") (pinfunction "PC2(ADC2/PCINT10)_25") (pintype "bidirectional"))
    )
    (net (code "67") (name "unconnected-(IC5-PC3(ADC3{slash}PCINT11)-Pad26)") (class "Default")
      (node (ref "IC5") (pin "26") (pinfunction "PC3(ADC3/PCINT11)_26") (pintype "bidirectional"))
    )
    (net (code "68") (name "unconnected-(IC5-PD3(INT1{slash}OC2B{slash}PCINT19)-Pad5)") (class "Default")
      (node (ref "IC5") (pin "5") (pinfunction "PD3(INT1/OC2B/PCINT19)_5") (pintype "bidirectional"))
    )
    (net (code "69") (name "unconnected-(IC5-PD5(T1{slash}OC0B{slash}PCINT21)-Pad11)") (class "Default")
      (node (ref "IC5") (pin "11") (pinfunction "PD5(T1/OC0B/PCINT21)_11") (pintype "bidirectional"))
    )
    (net (code "70") (name "unconnected-(K4B-O-Pad12)") (class "Default")
      (node (ref "K4") (pin "12") (pinfunction "O_12") (pintype "passive"))
    )
    (net (code "71") (name "unconnected-(K6B-O-Pad12)") (class "Default")
      (node (ref "K6") (pin "12") (pinfunction "O_12") (pintype "passive"))
    )
    (net (code "72") (name "unconnected-(X4-Pad1)") (class "Default")
      (node (ref "X4") (pin "1") (pinfunction "1_1") (pintype "passive"))
    )
    (net (code "73") (name "unconnected-(X4B-1-Pad2)") (class "Default")
      (node (ref "X4") (pin "2") (pinfunction "1_2") (pintype "passive"))
    )
    (net (code "74") (name "unconnected-(X5-Pad1)") (class "Default")
      (node (ref "X5") (pin "1") (pinfunction "1_1") (pintype "passive"))
    )
    (net (code "75") (name "unconnected-(X5B-1-Pad2)") (class "Default")
      (node (ref "X5") (pin "2") (pinfunction "1_2") (pintype "passive"))
    )
    (net (code "76") (name "unconnected-(X8-Pad1)") (class "Default")
      (node (ref "X8") (pin "1") (pinfunction "1_1") (pintype "passive"))
    )
    (net (code "77") (name "unconnected-(X8B-1-Pad2)") (class "Default")
      (node (ref "X8") (pin "2") (pinfunction "1_2") (pintype "passive"))
    )
    (net (code "78") (name "unconnected-(X8C-1-Pad3)") (class "Default")
      (node (ref "X8") (pin "3") (pinfunction "1_3") (pintype "passive"))
    )
    (net (code "79") (name "unconnected-(X8D-1-Pad4)") (class "Default")
      (node (ref "X8") (pin "4") (pinfunction "1_4") (pintype "passive"))
    )
  )
)
